# LED_and_Relay.net
KiCad netlist of a schematic drawn in Altium Designer
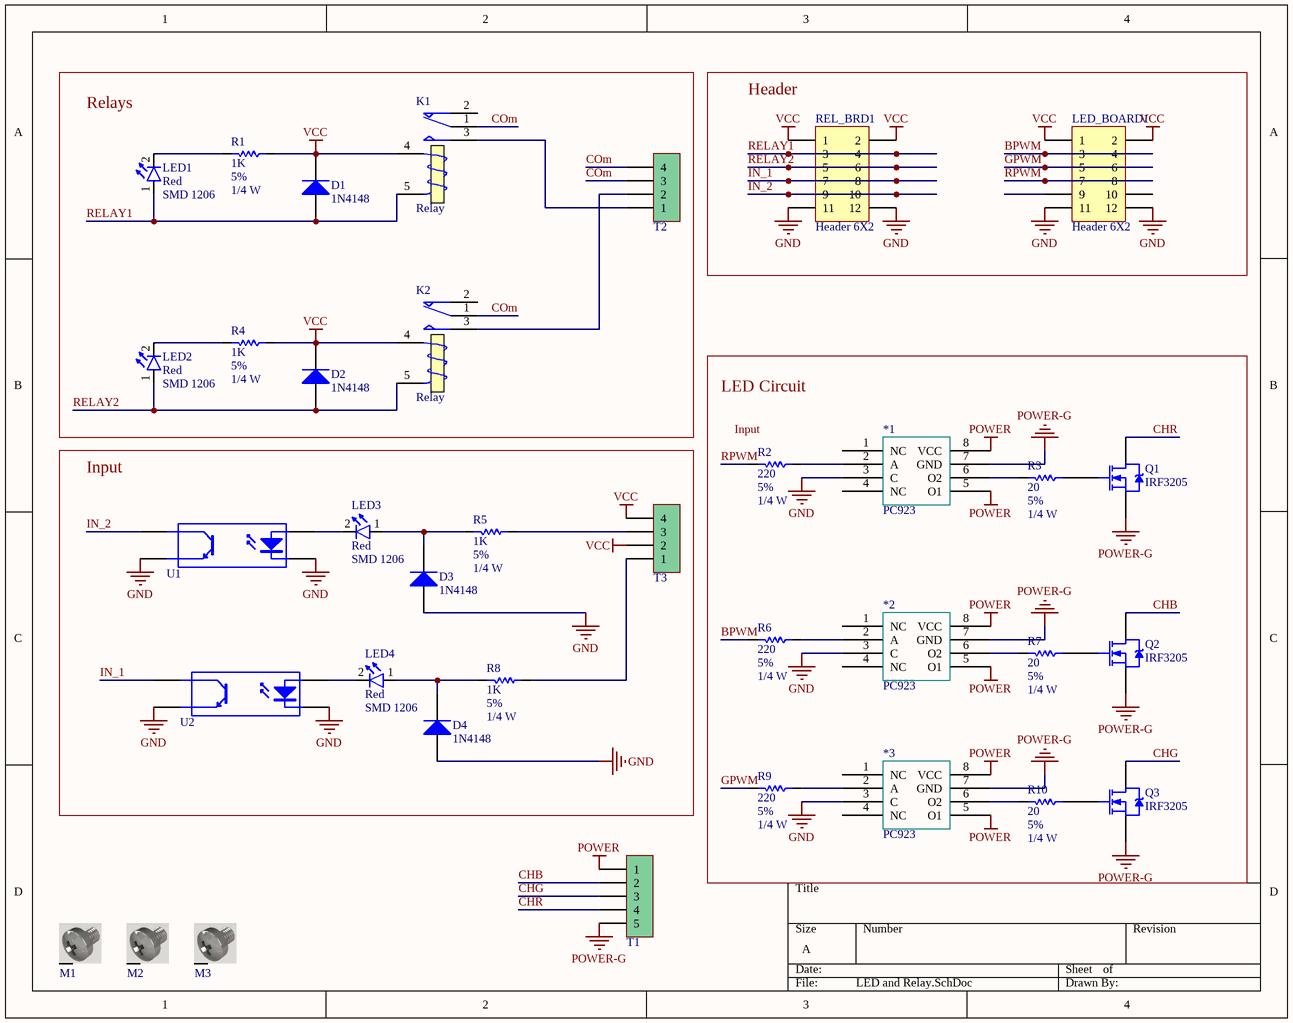
[diagram p0: LED and Relay.SchDoc]

(export (version "E")
  (design (tool "Eeschema 10.0.6"))
  (components
    (comp (ref "*1")
      (value "PC923")
      (footprint "PC923")
      (libsource (lib "Integrated_Library1") (part "PC923"))
    )
    (comp (ref "*2")
      (value "PC923")
      (footprint "PC923")
      (libsource (lib "Integrated_Library1") (part "PC923"))
    )
    (comp (ref "*3")
      (value "PC923")
      (footprint "PC923")
      (libsource (lib "Integrated_Library1") (part "PC923"))
    )
    (comp (ref "D1")
      (value "1N4148")
      (footprint "LL4148")
      (description "High Conductance Fast Diode")
      (fields (field (name "PUBLISHER") "Altium Limited"))
      (libsource (lib "My Library") (part "Diode 1N4148"))
    )
    (comp (ref "D2")
      (value "1N4148")
      (footprint "LL4148")
      (description "High Conductance Fast Diode")
      (fields (field (name "PUBLISHER") "Altium Limited"))
      (libsource (lib "My Library") (part "Diode 1N4148"))
    )
    (comp (ref "D3")
      (value "1N4148")
      (footprint "LL4148")
      (description "High Conductance Fast Diode")
      (fields (field (name "PUBLISHER") "Altium Limited"))
      (libsource (lib "My Library") (part "Diode 1N4148"))
    )
    (comp (ref "D4")
      (value "1N4148")
      (footprint "LL4148")
      (description "High Conductance Fast Diode")
      (fields (field (name "PUBLISHER") "Altium Limited"))
      (libsource (lib "My Library") (part "Diode 1N4148"))
    )
    (comp (ref "K1")
      (value "Relay")
      (footprint "Relay 15.40x12.10x13.10")
      (description "SPDT Relay")
      (fields (field (name "DESIGNER") "Eng. Saeid Jorablo"))
      (libsource (lib "My Library") (part "Relay"))
    )
    (comp (ref "K2")
      (value "Relay")
      (footprint "Relay 15.40x12.10x13.10")
      (description "SPDT Relay")
      (fields (field (name "DESIGNER") "Eng. Saeid Jorablo"))
      (libsource (lib "My Library") (part "Relay"))
    )
    (comp (ref "LED1")
      (value "Red")
      (footprint "LED SMD 1206")
      (description "LED")
      (fields
        (field (name "COLOR") "Red")
        (field (name "SIZE") "SMD 1206")
        (field (name "DESIGNER") "Saeid Jorablo")
      )
      (libsource (lib "My Library") (part "LED"))
    )
    (comp (ref "LED2")
      (value "Red")
      (footprint "LED SMD 1206")
      (description "LED")
      (fields
        (field (name "COLOR") "Red")
        (field (name "SIZE") "SMD 1206")
        (field (name "DESIGNER") "Saeid Jorablo")
      )
      (libsource (lib "My Library") (part "LED"))
    )
    (comp (ref "LED3")
      (value "Red")
      (footprint "LED SMD 1206")
      (description "LED")
      (fields
        (field (name "COLOR") "Red")
        (field (name "SIZE") "SMD 1206")
        (field (name "DESIGNER") "Saeid Jorablo")
      )
      (libsource (lib "My Library") (part "LED"))
    )
    (comp (ref "LED4")
      (value "Red")
      (footprint "LED SMD 1206")
      (description "LED")
      (fields
        (field (name "COLOR") "Red")
        (field (name "SIZE") "SMD 1206")
        (field (name "DESIGNER") "Saeid Jorablo")
      )
      (libsource (lib "My Library") (part "LED"))
    )
    (comp (ref "LED_BOARD1")
      (value "Header 6X2")
      (footprint "HDR2X6")
      (description "Header, 6-Pin, Dual row")
      (fields (field (name "PUBLISHER") "Altium Limited"))
      (libsource (lib "Miscellaneous Connectors") (part "Header 6X2"))
    )
    (comp (ref "M1")
      (value "Screw")
      (footprint "Board Screw_No Silk")
      (description "Board Screw With Spacer")
      (libsource (lib "My Library") (part "Board Screw"))
    )
    (comp (ref "M2")
      (value "Screw")
      (footprint "Board Screw_No Silk")
      (description "Board Screw With Spacer")
      (libsource (lib "My Library") (part "Board Screw"))
    )
    (comp (ref "M3")
      (value "Screw")
      (footprint "Board Screw_No Silk")
      (description "Board Screw With Spacer")
      (libsource (lib "My Library") (part "Board Screw"))
    )
    (comp (ref "Q1")
      (value "IRF3205")
      (footprint "TO-220AB")
      (description "HEXFET Power MOSFET")
      (fields (field (name "PUBLISHER") "Altium Limited"))
      (libsource (lib "IR Discrete MOSFET - Power") (part "IRF3205"))
    )
    (comp (ref "Q2")
      (value "IRF3205")
      (footprint "TO-220AB")
      (description "HEXFET Power MOSFET")
      (fields (field (name "PUBLISHER") "Altium Limited"))
      (libsource (lib "IR Discrete MOSFET - Power") (part "IRF3205"))
    )
    (comp (ref "Q3")
      (value "IRF3205")
      (footprint "TO-220AB")
      (description "HEXFET Power MOSFET")
      (fields (field (name "PUBLISHER") "Altium Limited"))
      (libsource (lib "IR Discrete MOSFET - Power") (part "IRF3205"))
    )
    (comp (ref "R1")
      (value "1K")
      (footprint "RES 1206 (3216X08L)")
      (description "Resistor")
      (fields (field (name "TOLERANCE") "5%") (field (name "POWER") "1/4 W"))
      (libsource (lib "My Library") (part "Resistor"))
    )
    (comp (ref "R2")
      (value "220")
      (footprint "RES 1206 (3216X08L)")
      (description "Resistor")
      (fields (field (name "TOLERANCE") "5%") (field (name "POWER") "1/4 W"))
      (libsource (lib "My Library") (part "Resistor"))
    )
    (comp (ref "R3")
      (value "20")
      (footprint "RES 1206 (3216X08L)")
      (description "Resistor")
      (fields (field (name "TOLERANCE") "5%") (field (name "POWER") "1/4 W"))
      (libsource (lib "My Library") (part "Resistor"))
    )
    (comp (ref "R4")
      (value "1K")
      (footprint "RES 1206 (3216X08L)")
      (description "Resistor")
      (fields (field (name "TOLERANCE") "5%") (field (name "POWER") "1/4 W"))
      (libsource (lib "My Library") (part "Resistor"))
    )
    (comp (ref "R5")
      (value "1K")
      (footprint "RES 1206 (3216X08L)")
      (description "Resistor")
      (fields (field (name "TOLERANCE") "5%") (field (name "POWER") "1/4 W"))
      (libsource (lib "My Library") (part "Resistor"))
    )
    (comp (ref "R6")
      (value "220")
      (footprint "RES 1206 (3216X08L)")
      (description "Resistor")
      (fields (field (name "TOLERANCE") "5%") (field (name "POWER") "1/4 W"))
      (libsource (lib "My Library") (part "Resistor"))
    )
    (comp (ref "R7")
      (value "20")
      (footprint "RES 1206 (3216X08L)")
      (description "Resistor")
      (fields (field (name "TOLERANCE") "5%") (field (name "POWER") "1/4 W"))
      (libsource (lib "My Library") (part "Resistor"))
    )
    (comp (ref "R8")
      (value "1K")
      (footprint "RES 1206 (3216X08L)")
      (description "Resistor")
      (fields (field (name "TOLERANCE") "5%") (field (name "POWER") "1/4 W"))
      (libsource (lib "My Library") (part "Resistor"))
    )
    (comp (ref "R9")
      (value "220")
      (footprint "RES 1206 (3216X08L)")
      (description "Resistor")
      (fields (field (name "TOLERANCE") "5%") (field (name "POWER") "1/4 W"))
      (libsource (lib "My Library") (part "Resistor"))
    )
    (comp (ref "R10")
      (value "20")
      (footprint "RES 1206 (3216X08L)")
      (description "Resistor")
      (fields (field (name "TOLERANCE") "5%") (field (name "POWER") "1/4 W"))
      (libsource (lib "My Library") (part "Resistor"))
    )
    (comp (ref "REL_BRD1")
      (value "Header 6X2")
      (footprint "HDR2X6")
      (description "Header, 6-Pin, Dual row")
      (fields (field (name "PUBLISHER") "Altium Limited"))
      (libsource (lib "Miscellaneous Connectors") (part "Header 6X2"))
    )
    (comp (ref "T1")
      (value "Phoenix terminal")
      (footprint "phoenix terminal 5")
      (description "Terminal 5 Pin")
      (fields (field (name "DESIGNER") "Seyed Mohsen Ghasemain") (field (name "E-MAIL") "picpars@gmail.com"))
      (libsource (lib "PicPars.com_usefully_Library") (part "Phoenix terminal 5"))
    )
    (comp (ref "T2")
      (value "Phoenix terminal")
      (footprint "phoenix terminal 4")
      (description "Terminal 4 Pin")
      (fields (field (name "DESIGNER") "Seyed Mohsen Ghasemain") (field (name "E-MAIL") "picpars@gmail.com"))
      (libsource (lib "PicPars.com_usefully_Library") (part "Phoenix terminal 4"))
    )
    (comp (ref "T3")
      (value "Phoenix terminal")
      (footprint "phoenix terminal 4")
      (description "Terminal 4 Pin")
      (fields (field (name "DESIGNER") "Seyed Mohsen Ghasemain") (field (name "E-MAIL") "picpars@gmail.com"))
      (libsource (lib "PicPars.com_usefully_Library") (part "Phoenix terminal 4"))
    )
    (comp (ref "U1")
      (value "Optoisolator")
      (footprint "My_opto")
      (libsource (lib "Mylib") (part "Optoisolator"))
    )
    (comp (ref "U2")
      (value "Optoisolator")
      (footprint "My_opto")
      (libsource (lib "Mylib") (part "Optoisolator"))
    )
  )
  (nets
    (net (code "1") (name "/BPWM") (class "Default")
      (node (ref "LED_BOARD1") (pin "3") (pinfunction "3_3") (pintype "passive"))
      (node (ref "LED_BOARD1") (pin "4") (pinfunction "4_4") (pintype "passive"))
      (node (ref "R6") (pin "2") (pinfunction "2_2") (pintype "passive"))
    )
    (net (code "2") (name "/CHB") (class "Default")
      (node (ref "Q2") (pin "2") (pinfunction "D_2") (pintype "passive"))
      (node (ref "T1") (pin "2") (pinfunction "2_2") (pintype "passive"))
    )
    (net (code "3") (name "/CHG") (class "Default")
      (node (ref "Q3") (pin "2") (pinfunction "D_2") (pintype "passive"))
      (node (ref "T1") (pin "3") (pinfunction "3_3") (pintype "passive"))
    )
    (net (code "4") (name "/CHR") (class "Default")
      (node (ref "Q1") (pin "2") (pinfunction "D_2") (pintype "passive"))
      (node (ref "T1") (pin "4") (pinfunction "4_4") (pintype "passive"))
    )
    (net (code "5") (name "/COm") (class "Default")
      (node (ref "K1") (pin "1") (pinfunction "COM_1") (pintype "passive"))
      (node (ref "K2") (pin "1") (pinfunction "COM_1") (pintype "passive"))
      (node (ref "T2") (pin "3") (pinfunction "3_3") (pintype "passive"))
      (node (ref "T2") (pin "4") (pinfunction "4_4") (pintype "passive"))
    )
    (net (code "6") (name "/GPWM") (class "Default")
      (node (ref "LED_BOARD1") (pin "5") (pinfunction "5_5") (pintype "passive"))
      (node (ref "LED_BOARD1") (pin "6") (pinfunction "6_6") (pintype "passive"))
      (node (ref "R9") (pin "2") (pinfunction "2_2") (pintype "passive"))
    )
    (net (code "8") (name "/IN_1") (class "Default")
      (node (ref "REL_BRD1") (pin "7") (pinfunction "7_7") (pintype "passive"))
      (node (ref "REL_BRD1") (pin "8") (pinfunction "8_8") (pintype "passive"))
      (node (ref "U2") (pin "3") (pinfunction "C_3") (pintype "passive"))
    )
    (net (code "9") (name "/IN_2") (class "Default")
      (node (ref "REL_BRD1") (pin "10") (pinfunction "10_10") (pintype "passive"))
      (node (ref "REL_BRD1") (pin "9") (pinfunction "9_9") (pintype "passive"))
      (node (ref "U1") (pin "3") (pinfunction "C_3") (pintype "passive"))
    )
    (net (code "12") (name "/RELAY1") (class "Default")
      (node (ref "D1") (pin "1") (pinfunction "A_1") (pintype "passive"))
      (node (ref "K1") (pin "5") (pinfunction "T2_5") (pintype "passive"))
      (node (ref "LED1") (pin "1") (pinfunction "A_1") (pintype "passive"))
      (node (ref "REL_BRD1") (pin "3") (pinfunction "3_3") (pintype "passive"))
      (node (ref "REL_BRD1") (pin "4") (pinfunction "4_4") (pintype "passive"))
    )
    (net (code "13") (name "/RELAY2") (class "Default")
      (node (ref "D2") (pin "1") (pinfunction "A_1") (pintype "passive"))
      (node (ref "K2") (pin "5") (pinfunction "T2_5") (pintype "passive"))
      (node (ref "LED2") (pin "1") (pinfunction "A_1") (pintype "passive"))
      (node (ref "REL_BRD1") (pin "5") (pinfunction "5_5") (pintype "passive"))
      (node (ref "REL_BRD1") (pin "6") (pinfunction "6_6") (pintype "passive"))
    )
    (net (code "14") (name "/RPWM") (class "Default")
      (node (ref "LED_BOARD1") (pin "7") (pinfunction "7_7") (pintype "passive"))
      (node (ref "LED_BOARD1") (pin "8") (pinfunction "8_8") (pintype "passive"))
      (node (ref "R2") (pin "2") (pinfunction "2_2") (pintype "passive"))
    )
    (net (code "16") (name "GND") (class "Default")
      (node (ref "*1") (pin "3") (pinfunction "C_3") (pintype "passive"))
      (node (ref "*2") (pin "3") (pinfunction "C_3") (pintype "passive"))
      (node (ref "*3") (pin "3") (pinfunction "C_3") (pintype "passive"))
      (node (ref "D3") (pin "1") (pinfunction "A_1") (pintype "passive"))
      (node (ref "D4") (pin "1") (pinfunction "A_1") (pintype "passive"))
      (node (ref "LED_BOARD1") (pin "11") (pinfunction "11_11") (pintype "passive"))
      (node (ref "LED_BOARD1") (pin "12") (pinfunction "12_12") (pintype "passive"))
      (node (ref "REL_BRD1") (pin "11") (pinfunction "11_11") (pintype "passive"))
      (node (ref "REL_BRD1") (pin "12") (pinfunction "12_12") (pintype "passive"))
      (node (ref "U1") (pin "2") (pinfunction "K_2") (pintype "passive"))
      (node (ref "U1") (pin "4") (pinfunction "E_4") (pintype "passive"))
      (node (ref "U2") (pin "2") (pinfunction "K_2") (pintype "passive"))
      (node (ref "U2") (pin "4") (pinfunction "E_4") (pintype "passive"))
    )
    (net (code "17") (name "Net-(*1-A)") (class "Default")
      (node (ref "*1") (pin "2") (pinfunction "A_2") (pintype "passive"))
      (node (ref "R2") (pin "1") (pinfunction "1_1") (pintype "passive"))
    )
    (net (code "18") (name "Net-(*1-O2)") (class "Default")
      (node (ref "*1") (pin "6") (pinfunction "O2_6") (pintype "passive"))
      (node (ref "R3") (pin "2") (pinfunction "2_2") (pintype "passive"))
    )
    (net (code "19") (name "Net-(*2-A)") (class "Default")
      (node (ref "*2") (pin "2") (pinfunction "A_2") (pintype "passive"))
      (node (ref "R6") (pin "1") (pinfunction "1_1") (pintype "passive"))
    )
    (net (code "20") (name "Net-(*2-O2)") (class "Default")
      (node (ref "*2") (pin "6") (pinfunction "O2_6") (pintype "passive"))
      (node (ref "R7") (pin "2") (pinfunction "2_2") (pintype "passive"))
    )
    (net (code "21") (name "Net-(*3-A)") (class "Default")
      (node (ref "*3") (pin "2") (pinfunction "A_2") (pintype "passive"))
      (node (ref "R9") (pin "1") (pinfunction "1_1") (pintype "passive"))
    )
    (net (code "22") (name "Net-(*3-O2)") (class "Default")
      (node (ref "*3") (pin "6") (pinfunction "O2_6") (pintype "passive"))
      (node (ref "R10") (pin "2") (pinfunction "2_2") (pintype "passive"))
    )
    (net (code "23") (name "Net-(D3-K)") (class "Default")
      (node (ref "D3") (pin "2") (pinfunction "K_2") (pintype "passive"))
      (node (ref "LED3") (pin "1") (pinfunction "A_1") (pintype "passive"))
      (node (ref "R5") (pin "1") (pinfunction "1_1") (pintype "passive"))
    )
    (net (code "24") (name "Net-(D4-K)") (class "Default")
      (node (ref "D4") (pin "2") (pinfunction "K_2") (pintype "passive"))
      (node (ref "LED4") (pin "1") (pinfunction "A_1") (pintype "passive"))
      (node (ref "R8") (pin "1") (pinfunction "1_1") (pintype "passive"))
    )
    (net (code "25") (name "Net-(K1-NO)") (class "Default")
      (node (ref "K1") (pin "3") (pinfunction "NO_3") (pintype "passive"))
      (node (ref "T2") (pin "1") (pinfunction "1_1") (pintype "passive"))
    )
    (net (code "26") (name "Net-(K2-NO)") (class "Default")
      (node (ref "K2") (pin "3") (pinfunction "NO_3") (pintype "passive"))
      (node (ref "T2") (pin "2") (pinfunction "2_2") (pintype "passive"))
    )
    (net (code "27") (name "Net-(LED1-K)") (class "Default")
      (node (ref "LED1") (pin "2") (pinfunction "K_2") (pintype "passive"))
      (node (ref "R1") (pin "2") (pinfunction "2_2") (pintype "passive"))
    )
    (net (code "28") (name "Net-(LED2-K)") (class "Default")
      (node (ref "LED2") (pin "2") (pinfunction "K_2") (pintype "passive"))
      (node (ref "R4") (pin "2") (pinfunction "2_2") (pintype "passive"))
    )
    (net (code "29") (name "Net-(LED3-K)") (class "Default")
      (node (ref "LED3") (pin "2") (pinfunction "K_2") (pintype "passive"))
      (node (ref "U1") (pin "1") (pinfunction "A_1") (pintype "passive"))
    )
    (net (code "30") (name "Net-(LED4-K)") (class "Default")
      (node (ref "LED4") (pin "2") (pinfunction "K_2") (pintype "passive"))
      (node (ref "U2") (pin "1") (pinfunction "A_1") (pintype "passive"))
    )
    (net (code "31") (name "Net-(Q1-G)") (class "Default")
      (node (ref "Q1") (pin "1") (pinfunction "G_1") (pintype "passive"))
      (node (ref "R3") (pin "1") (pinfunction "1_1") (pintype "passive"))
    )
    (net (code "32") (name "Net-(Q2-G)") (class "Default")
      (node (ref "Q2") (pin "1") (pinfunction "G_1") (pintype "passive"))
      (node (ref "R7") (pin "1") (pinfunction "1_1") (pintype "passive"))
    )
    (net (code "33") (name "Net-(Q3-G)") (class "Default")
      (node (ref "Q3") (pin "1") (pinfunction "G_1") (pintype "passive"))
      (node (ref "R10") (pin "1") (pinfunction "1_1") (pintype "passive"))
    )
    (net (code "34") (name "Net-(R5-Pad2)") (class "Default")
      (node (ref "R5") (pin "2") (pinfunction "2_2") (pintype "passive"))
      (node (ref "T3") (pin "3") (pinfunction "3_3") (pintype "passive"))
    )
    (net (code "35") (name "Net-(R8-Pad2)") (class "Default")
      (node (ref "R8") (pin "2") (pinfunction "2_2") (pintype "passive"))
      (node (ref "T3") (pin "1") (pinfunction "1_1") (pintype "passive"))
    )
    (net (code "36") (name "POWER") (class "Default")
      (node (ref "*1") (pin "5") (pinfunction "O1_5") (pintype "passive"))
      (node (ref "*1") (pin "8") (pinfunction "VCC_8") (pintype "passive"))
      (node (ref "*2") (pin "5") (pinfunction "O1_5") (pintype "passive"))
      (node (ref "*2") (pin "8") (pinfunction "VCC_8") (pintype "passive"))
      (node (ref "*3") (pin "5") (pinfunction "O1_5") (pintype "passive"))
      (node (ref "*3") (pin "8") (pinfunction "VCC_8") (pintype "passive"))
      (node (ref "T1") (pin "1") (pinfunction "1_1") (pintype "passive"))
    )
    (net (code "37") (name "POWER-G") (class "Default")
      (node (ref "*1") (pin "7") (pinfunction "GND_7") (pintype "passive"))
      (node (ref "*2") (pin "7") (pinfunction "GND_7") (pintype "passive"))
      (node (ref "*3") (pin "7") (pinfunction "GND_7") (pintype "passive"))
      (node (ref "Q1") (pin "3") (pinfunction "S_3") (pintype "passive"))
      (node (ref "Q2") (pin "3") (pinfunction "S_3") (pintype "passive"))
      (node (ref "Q3") (pin "3") (pinfunction "S_3") (pintype "passive"))
      (node (ref "T1") (pin "5") (pinfunction "5_5") (pintype "passive"))
    )
    (net (code "38") (name "VCC") (class "Default")
      (node (ref "D1") (pin "2") (pinfunction "K_2") (pintype "passive"))
      (node (ref "D2") (pin "2") (pinfunction "K_2") (pintype "passive"))
      (node (ref "K1") (pin "4") (pinfunction "T1_4") (pintype "passive"))
      (node (ref "K2") (pin "4") (pinfunction "T1_4") (pintype "passive"))
      (node (ref "LED_BOARD1") (pin "1") (pinfunction "1_1") (pintype "passive"))
      (node (ref "LED_BOARD1") (pin "2") (pinfunction "2_2") (pintype "passive"))
      (node (ref "R1") (pin "1") (pinfunction "1_1") (pintype "passive"))
      (node (ref "R4") (pin "1") (pinfunction "1_1") (pintype "passive"))
      (node (ref "REL_BRD1") (pin "1") (pinfunction "1_1") (pintype "passive"))
      (node (ref "REL_BRD1") (pin "2") (pinfunction "2_2") (pintype "passive"))
      (node (ref "T3") (pin "2") (pinfunction "2_2") (pintype "passive"))
      (node (ref "T3") (pin "4") (pinfunction "4_4") (pintype "passive"))
    )
    (net (code "39") (name "unconnected-(*1-NC-Pad1)") (class "Default")
      (node (ref "*1") (pin "1") (pinfunction "NC_1") (pintype "passive"))
    )
    (net (code "40") (name "unconnected-(*1-NC-Pad4)") (class "Default")
      (node (ref "*1") (pin "4") (pinfunction "NC_4") (pintype "passive"))
    )
    (net (code "41") (name "unconnected-(*2-NC-Pad1)") (class "Default")
      (node (ref "*2") (pin "1") (pinfunction "NC_1") (pintype "passive"))
    )
    (net (code "42") (name "unconnected-(*2-NC-Pad4)") (class "Default")
      (node (ref "*2") (pin "4") (pinfunction "NC_4") (pintype "passive"))
    )
    (net (code "43") (name "unconnected-(*3-NC-Pad1)") (class "Default")
      (node (ref "*3") (pin "1") (pinfunction "NC_1") (pintype "passive"))
    )
    (net (code "44") (name "unconnected-(*3-NC-Pad4)") (class "Default")
      (node (ref "*3") (pin "4") (pinfunction "NC_4") (pintype "passive"))
    )
    (net (code "45") (name "unconnected-(K1-NC-Pad2)") (class "Default")
      (node (ref "K1") (pin "2") (pinfunction "NC_2") (pintype "passive"))
    )
    (net (code "46") (name "unconnected-(K2-NC-Pad2)") (class "Default")
      (node (ref "K2") (pin "2") (pinfunction "NC_2") (pintype "passive"))
    )
    (net (code "47") (name "unconnected-(LED_BOARD1-Pad9)") (class "Default")
      (node (ref "LED_BOARD1") (pin "9") (pinfunction "9_9") (pintype "passive"))
    )
    (net (code "48") (name "unconnected-(LED_BOARD1-Pad10)") (class "Default")
      (node (ref "LED_BOARD1") (pin "10") (pinfunction "10_10") (pintype "passive"))
    )
    (net (code "49") (name "unconnected-(M1-PadS)") (class "Default")
      (node (ref "M1") (pin "S") (pinfunction "S_S") (pintype "passive"))
    )
    (net (code "50") (name "unconnected-(M2-PadS)") (class "Default")
      (node (ref "M2") (pin "S") (pinfunction "S_S") (pintype "passive"))
    )
    (net (code "51") (name "unconnected-(M3-PadS)") (class "Default")
      (node (ref "M3") (pin "S") (pinfunction "S_S") (pintype "passive"))
    )
  )
)
